# PowerSupply-5V-3_3V-SparkFun-v11.net
KiCad netlist of a schematic drawn in EAGLE
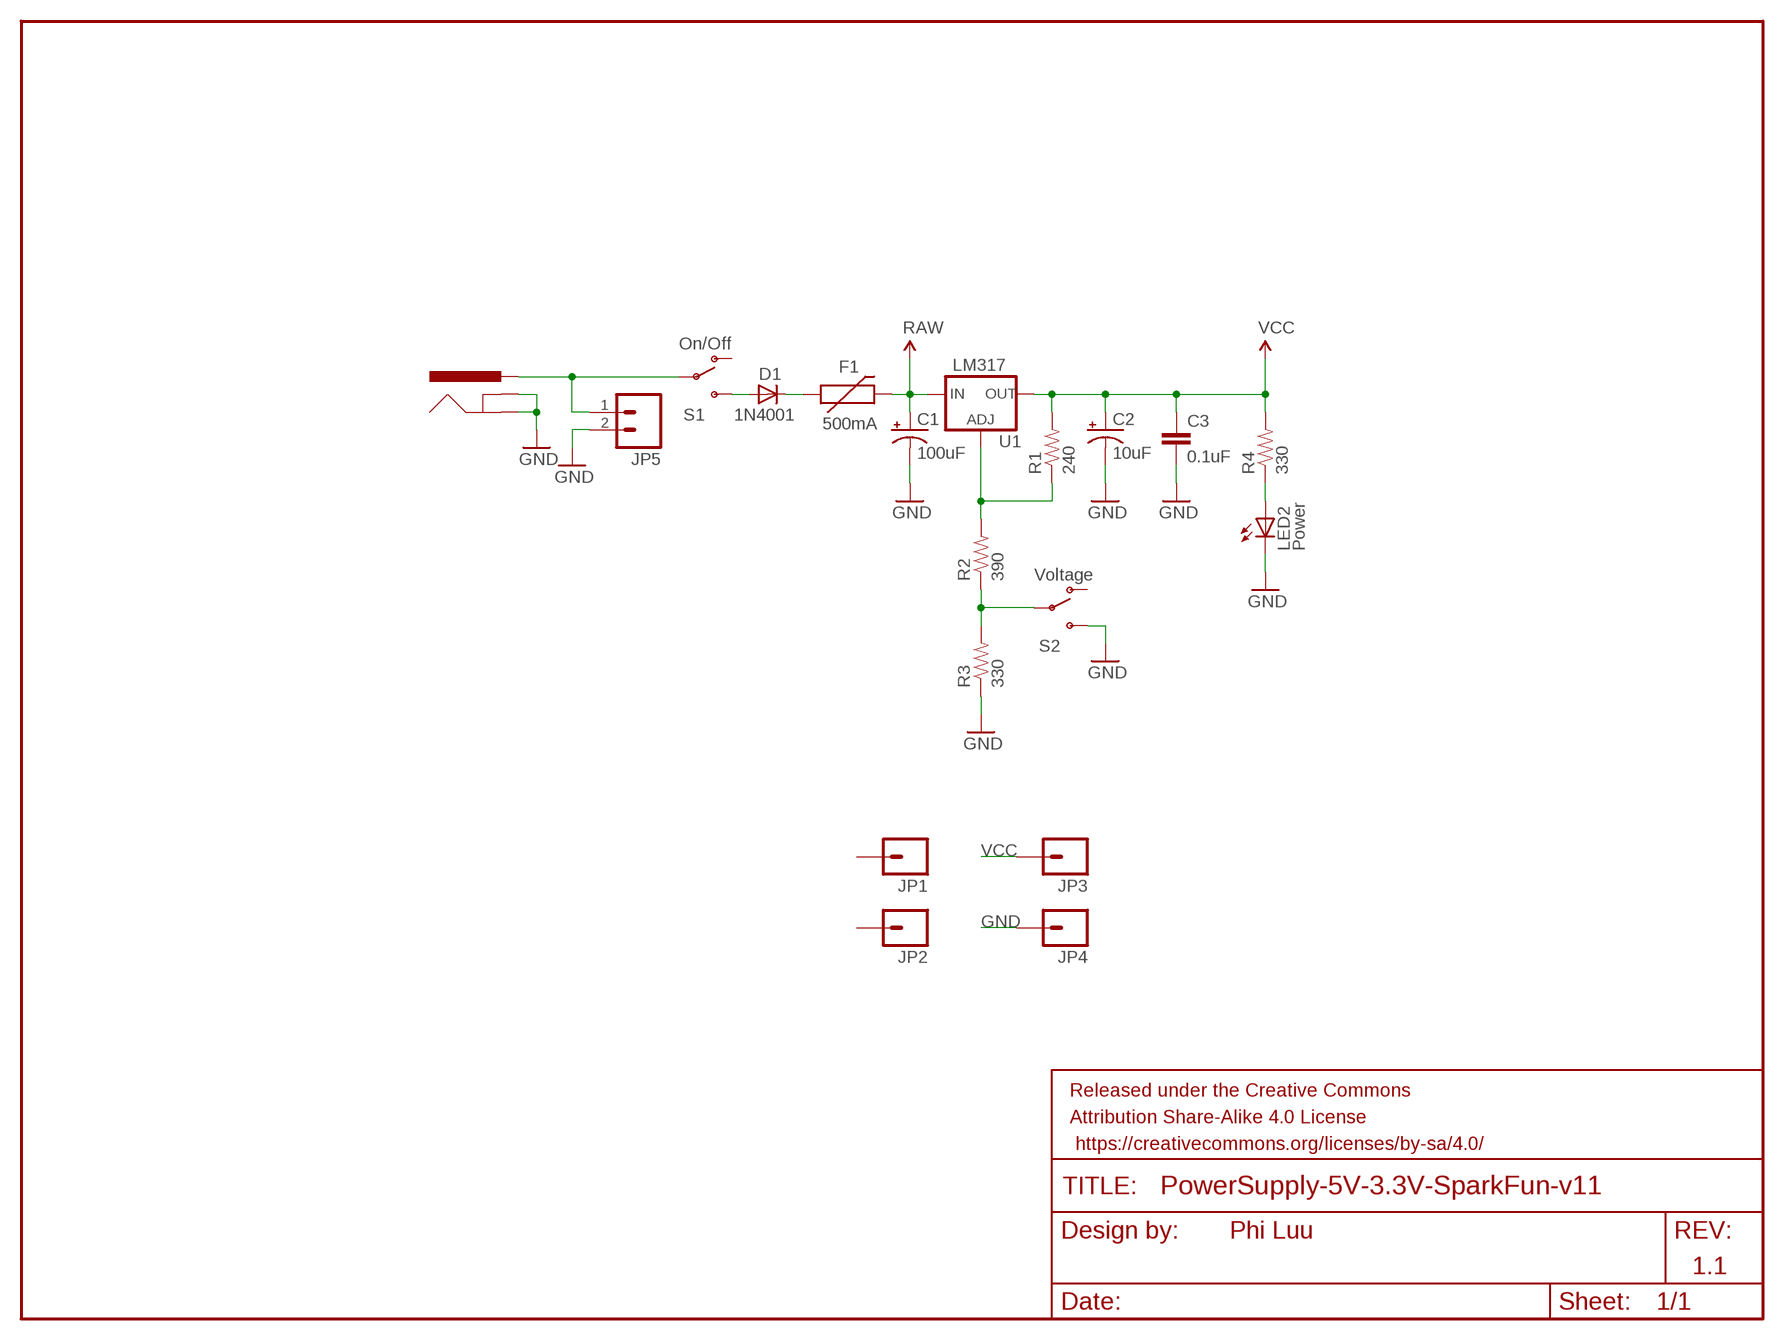
[diagram p0: schematic, sheet 1]

(export (version "E")
  (design (tool "Eeschema 10.0.6"))
  (components
    (comp (ref "C1")
      (value "100uF")
      (footprint "eagle-import:CPOL-RADIAL-100UF-25V")
      (libsource (lib "eagle-import") (part "CAP_POLPTH1"))
    )
    (comp (ref "C2")
      (value "10uF")
      (footprint "eagle-import:CPOL-RADIAL-10UF-25V")
      (libsource (lib "eagle-import") (part "CAP_POLPTH2"))
    )
    (comp (ref "C3")
      (value "0.1uF")
      (footprint "eagle-import:CAP-PTH-SMALL2")
      (libsource (lib "eagle-import") (part "CAPPTH2"))
    )
    (comp (ref "D1")
      (value "1N4001")
      (footprint "eagle-import:DIODE-0.4")
      (libsource (lib "eagle-import") (part "DIODEPTH"))
    )
    (comp (ref "F1")
      (value "500mA")
      (footprint "eagle-import:PTC")
      (libsource (lib "eagle-import") (part "PTCPTH"))
    )
    (comp (ref "FRAME1")
      (value "FRAME-LETTER")
      (footprint "eagle-import:CREATIVE_COMMONS")
      (libsource (lib "eagle-import") (part "FRAME-LETTER"))
    )
    (comp (ref "J1")
      (value "POWER_JACKPTH")
      (footprint "eagle-import:POWER_JACK_PTH")
      (libsource (lib "eagle-import") (part "POWER_JACKPTH"))
    )
    (comp (ref "JP1")
      (value "M01PTH")
      (footprint "eagle-import:1X01")
      (libsource (lib "eagle-import") (part "M01PTH"))
    )
    (comp (ref "JP2")
      (value "M01PTH")
      (footprint "eagle-import:1X01")
      (libsource (lib "eagle-import") (part "M01PTH"))
    )
    (comp (ref "JP3")
      (value "M01PTH")
      (footprint "eagle-import:1X01")
      (libsource (lib "eagle-import") (part "M01PTH"))
    )
    (comp (ref "JP4")
      (value "M01PTH")
      (footprint "eagle-import:1X01")
      (libsource (lib "eagle-import") (part "M01PTH"))
    )
    (comp (ref "JP5")
      (value "M02PTH")
      (footprint "eagle-import:1X02")
      (libsource (lib "eagle-import") (part "M02PTH"))
    )
    (comp (ref "LED2")
      (value "Power")
      (footprint "eagle-import:LED5MM")
      (libsource (lib "eagle-import") (part "LED5MM"))
    )
    (comp (ref "R1")
      (value "240")
      (footprint "eagle-import:AXIAL-0.3")
      (libsource (lib "eagle-import") (part "RESISTORPTH1"))
    )
    (comp (ref "R2")
      (value "390")
      (footprint "eagle-import:AXIAL-0.3")
      (libsource (lib "eagle-import") (part "RESISTORPTH1"))
    )
    (comp (ref "R3")
      (value "330")
      (footprint "eagle-import:AXIAL-0.3")
      (libsource (lib "eagle-import") (part "RESISTORPTH1"))
    )
    (comp (ref "R4")
      (value "330")
      (footprint "eagle-import:AXIAL-0.3")
      (libsource (lib "eagle-import") (part "RESISTORPTH1"))
    )
    (comp (ref "S1")
      (value "On/Off")
      (footprint "eagle-import:SWITCH-SPST")
      (libsource (lib "eagle-import") (part "SWITCH-SPSTPTH"))
    )
    (comp (ref "S2")
      (value "Voltage")
      (footprint "eagle-import:SWITCH-SPST")
      (libsource (lib "eagle-import") (part "SWITCH-SPSTPTH"))
    )
    (comp (ref "U1")
      (value "LM317")
      (footprint "eagle-import:TO220-ADJ")
      (libsource (lib "eagle-import") (part "V_REG_317SINK"))
    )
  )
  (nets
    (net (code "1") (name "GND") (class "Default")
      (node (ref "C1") (pin "2") (pinfunction "-_2") (pintype "passive"))
      (node (ref "C2") (pin "2") (pinfunction "-_2") (pintype "passive"))
      (node (ref "C3") (pin "2") (pinfunction "2_2") (pintype "passive"))
      (node (ref "J1") (pin "GND") (pinfunction "GND_GND") (pintype "bidirectional"))
      (node (ref "J1") (pin "GNDBREAK") (pinfunction "GNDBREAK_GNDBREAK") (pintype "bidirectional"))
      (node (ref "JP4") (pin "1") (pinfunction "1_1") (pintype "passive"))
      (node (ref "JP5") (pin "2") (pinfunction "2_2") (pintype "passive"))
      (node (ref "LED2") (pin "K") (pinfunction "C_K") (pintype "passive"))
      (node (ref "R3") (pin "P$1") (pinfunction "1_P$1") (pintype "passive"))
      (node (ref "S2") (pin "3") (pinfunction "S_3") (pintype "passive"))
    )
    (net (code "2") (name "Net-(F1-1)") (class "Default")
      (node (ref "D1") (pin "C") (pinfunction "C_C") (pintype "passive"))
      (node (ref "F1") (pin "P$1") (pinfunction "1_P$1") (pintype "bidirectional"))
    )
    (net (code "3") (name "Net-(R1-1)") (class "Default")
      (node (ref "R1") (pin "P$1") (pinfunction "1_P$1") (pintype "passive"))
      (node (ref "R2") (pin "P$2") (pinfunction "2_P$2") (pintype "passive"))
      (node (ref "U1") (pin "ADJ") (pinfunction "ADJ_ADJ") (pintype "input"))
    )
    (net (code "4") (name "Net-(R2-1)") (class "Default")
      (node (ref "R2") (pin "P$1") (pinfunction "1_P$1") (pintype "passive"))
      (node (ref "R3") (pin "P$2") (pinfunction "2_P$2") (pintype "passive"))
      (node (ref "S2") (pin "2") (pinfunction "P_2") (pintype "passive"))
    )
    (net (code "5") (name "Net-(R4-1)") (class "Default")
      (node (ref "LED2") (pin "A") (pinfunction "A_A") (pintype "passive"))
      (node (ref "R4") (pin "P$1") (pinfunction "1_P$1") (pintype "passive"))
    )
    (net (code "6") (name "Net-(S1-P)") (class "Default")
      (node (ref "J1") (pin "PWR") (pinfunction "PWR_PWR") (pintype "bidirectional"))
      (node (ref "JP5") (pin "1") (pinfunction "1_1") (pintype "passive"))
      (node (ref "S1") (pin "2") (pinfunction "P_2") (pintype "passive"))
    )
    (net (code "7") (name "Net-(S1-S)") (class "Default")
      (node (ref "D1") (pin "A") (pinfunction "A_A") (pintype "passive"))
      (node (ref "S1") (pin "3") (pinfunction "S_3") (pintype "passive"))
    )
    (net (code "8") (name "RAW") (class "Default")
      (node (ref "C1") (pin "1") (pinfunction "+_1") (pintype "passive"))
      (node (ref "F1") (pin "P$2") (pinfunction "2_P$2") (pintype "bidirectional"))
      (node (ref "U1") (pin "IN") (pinfunction "IN_IN") (pintype "input"))
    )
    (net (code "9") (name "VCC") (class "Default")
      (node (ref "C2") (pin "1") (pinfunction "+_1") (pintype "passive"))
      (node (ref "C3") (pin "1") (pinfunction "1_1") (pintype "passive"))
      (node (ref "JP3") (pin "1") (pinfunction "1_1") (pintype "passive"))
      (node (ref "R1") (pin "P$2") (pinfunction "2_P$2") (pintype "passive"))
      (node (ref "R4") (pin "P$2") (pinfunction "2_P$2") (pintype "passive"))
      (node (ref "U1") (pin "OUT") (pinfunction "OUT_OUT") (pintype "output"))
    )
    (net (code "10") (name "unconnected-(JP1-Pad1)") (class "Default")
      (node (ref "JP1") (pin "1") (pinfunction "1_1") (pintype "passive"))
    )
    (net (code "11") (name "unconnected-(JP2-Pad1)") (class "Default")
      (node (ref "JP2") (pin "1") (pinfunction "1_1") (pintype "passive"))
    )
    (net (code "12") (name "unconnected-(S1-O-Pad1)") (class "Default")
      (node (ref "S1") (pin "1") (pinfunction "O_1") (pintype "passive"))
    )
    (net (code "13") (name "unconnected-(S2-O-Pad1)") (class "Default")
      (node (ref "S2") (pin "1") (pinfunction "O_1") (pintype "passive"))
    )
  )
)
